# Sheet3.net
KiCad netlist of a schematic drawn in Altium Designer
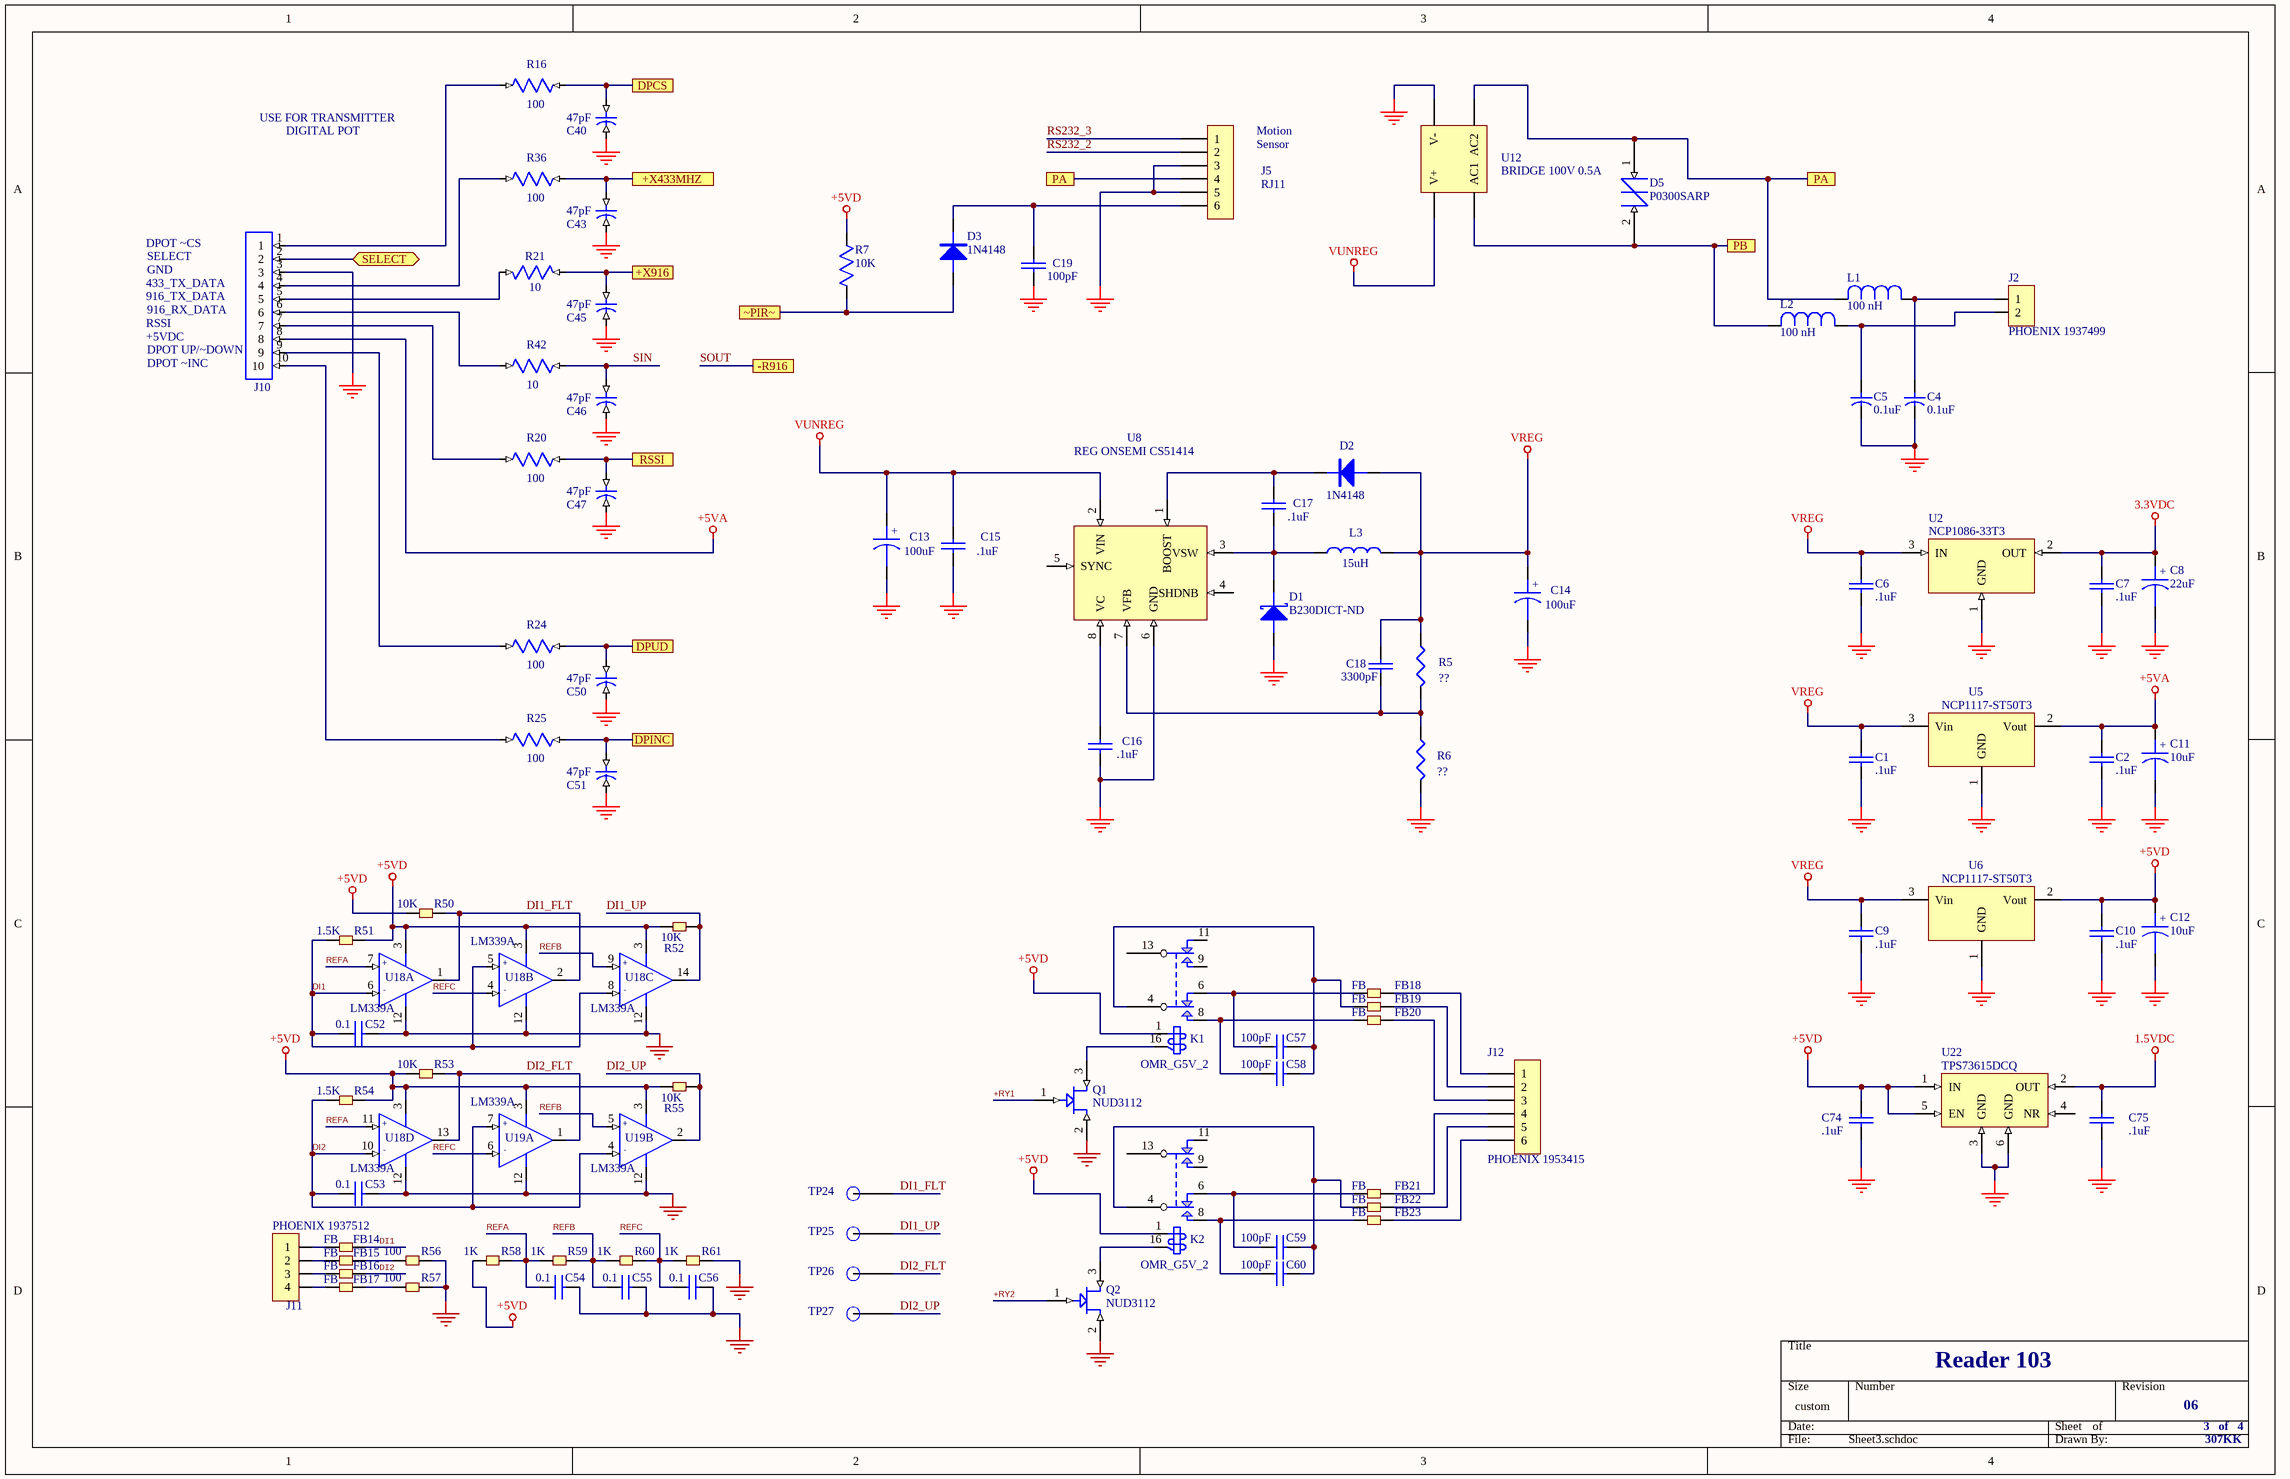
[diagram p0: Sheet3.schdoc]

(export (version "E")
  (design (tool "Eeschema 10.0.6"))
  (components
    (comp (ref "C1")
      (value ".1uF")
      (footprint "0603")
      (description "Capacitor")
      (libsource (lib "*") (part "CAP"))
    )
    (comp (ref "C2")
      (value ".1uF")
      (footprint "0603")
      (description "Capacitor")
      (libsource (lib "*") (part "CAP"))
    )
    (comp (ref "C4") (value "0.1uF") (footprint "0603") (libsource (lib "*") (part "C_0603")))
    (comp (ref "C5") (value "0.1uF") (footprint "0603") (libsource (lib "*") (part "C_0603")))
    (comp (ref "C6")
      (value ".1uF")
      (footprint "0603")
      (description "Capacitor")
      (libsource (lib "*") (part "CAP"))
    )
    (comp (ref "C7")
      (value ".1uF")
      (footprint "0603")
      (description "Capacitor")
      (libsource (lib "*") (part "CAP"))
    )
    (comp (ref "C8")
      (value "22uF")
      (footprint "CAP A CASE")
      (description "Capacitor")
      (libsource (lib "*") (part "CAPACITOR POL"))
    )
    (comp (ref "C9")
      (value ".1uF")
      (footprint "0603")
      (description "Capacitor")
      (libsource (lib "*") (part "CAP"))
    )
    (comp (ref "C10")
      (value ".1uF")
      (footprint "0603")
      (description "Capacitor")
      (libsource (lib "*") (part "CAP"))
    )
    (comp (ref "C11")
      (value "10uF")
      (footprint "CAP A CASE")
      (description "Capacitor")
      (libsource (lib "*") (part "CAPACITOR POL"))
    )
    (comp (ref "C12")
      (value "10uF")
      (footprint "CAP A CASE")
      (description "Capacitor")
      (libsource (lib "*") (part "CAPACITOR POL"))
    )
    (comp (ref "C13")
      (value "100uF")
      (footprint "CAP D CASE")
      (description "Capacitor")
      (libsource (lib "*") (part "CAPACITOR POL"))
    )
    (comp (ref "C14")
      (value "100uF")
      (footprint "CAP D CASE")
      (description "Capacitor")
      (libsource (lib "*") (part "CAPACITOR POL"))
    )
    (comp (ref "C15")
      (value ".1uF")
      (footprint "0603")
      (description "Capacitor")
      (libsource (lib "*") (part "CAP"))
    )
    (comp (ref "C16")
      (value ".1uF")
      (footprint "0603")
      (description "Capacitor")
      (libsource (lib "*") (part "CAP"))
    )
    (comp (ref "C17")
      (value ".1uF")
      (footprint "0603")
      (description "Capacitor")
      (libsource (lib "*") (part "CAP"))
    )
    (comp (ref "C18")
      (value "3300pF")
      (footprint "0603")
      (description "Capacitor")
      (libsource (lib "*") (part "CAP"))
    )
    (comp (ref "C19")
      (value "100pF")
      (footprint "0603")
      (description "Capacitor")
      (libsource (lib "*") (part "CAP"))
    )
    (comp (ref "C40") (value "47pF") (footprint "C0603") (libsource (lib "*") (part "C0603")))
    (comp (ref "C43") (value "47pF") (footprint "C0603") (libsource (lib "*") (part "C0603")))
    (comp (ref "C45") (value "47pF") (footprint "C0603") (libsource (lib "*") (part "C0603")))
    (comp (ref "C46") (value "47pF") (footprint "C0603") (libsource (lib "*") (part "C0603")))
    (comp (ref "C47") (value "47pF") (footprint "C0603") (libsource (lib "*") (part "C0603")))
    (comp (ref "C50") (value "47pF") (footprint "C0603") (libsource (lib "*") (part "C0603")))
    (comp (ref "C51") (value "47pF") (footprint "C0603") (libsource (lib "*") (part "C0603")))
    (comp (ref "C52") (value "0.1") (footprint "0805") (libsource (lib "*") (part "CAP NP_1")))
    (comp (ref "C53") (value "0.1") (footprint "0805") (libsource (lib "*") (part "CAP NP_1")))
    (comp (ref "C54") (value "0.1") (footprint "0805") (libsource (lib "*") (part "CAP NP_1")))
    (comp (ref "C55") (value "0.1") (footprint "0805") (libsource (lib "*") (part "CAP NP_1")))
    (comp (ref "C56") (value "0.1") (footprint "0805") (libsource (lib "*") (part "CAP NP_1")))
    (comp (ref "C57") (value "100pF") (footprint "SM/C_0805") (libsource (lib "*") (part "CAP NP_1")))
    (comp (ref "C58") (value "100pF") (footprint "SM/C_0805") (libsource (lib "*") (part "CAP NP_1")))
    (comp (ref "C59") (value "100pF") (footprint "SM/C_0805") (libsource (lib "*") (part "CAP NP_1")))
    (comp (ref "C60") (value "100pF") (footprint "SM/C_0805") (libsource (lib "*") (part "CAP NP_1")))
    (comp (ref "C74")
      (value ".1uF")
      (footprint "0603")
      (description "Capacitor")
      (libsource (lib "*") (part "CAP"))
    )
    (comp (ref "C75")
      (value ".1uF")
      (footprint "0603")
      (description "Capacitor")
      (libsource (lib "*") (part "CAP"))
    )
    (comp (ref "D1")
      (value "B230DICT-ND")
      (footprint "DIODE SMB")
      (description "Schottky Diode")
      (libsource (lib "*") (part "DIODE SCHOTTKY"))
    )
    (comp (ref "D2")
      (value "1N4148")
      (footprint "SOD123")
      (description "Diode")
      (libsource (lib "*") (part "DIODE"))
    )
    (comp (ref "D3")
      (value "1N4148")
      (footprint "SOD123")
      (description "Diode")
      (libsource (lib "*") (part "DIODE"))
    )
    (comp (ref "D5") (value "P0300SARP") (footprint "TRANSORB_1") (libsource (lib "*") (part "TRANSORB")))
    (comp (ref "FB14") (value "FB") (footprint "0603") (libsource (lib "*") (part "FB")))
    (comp (ref "FB15") (value "FB") (footprint "0603") (libsource (lib "*") (part "FB")))
    (comp (ref "FB16") (value "FB") (footprint "0603") (libsource (lib "*") (part "FB")))
    (comp (ref "FB17") (value "FB") (footprint "0603") (libsource (lib "*") (part "FB")))
    (comp (ref "FB18") (value "FB") (footprint "SM/R_1206") (libsource (lib "*") (part "FB")))
    (comp (ref "FB19") (value "FB") (footprint "SM/R_1206") (libsource (lib "*") (part "FB")))
    (comp (ref "FB20") (value "FB") (footprint "SM/R_1206") (libsource (lib "*") (part "FB")))
    (comp (ref "FB21") (value "FB") (footprint "SM/R_1206") (libsource (lib "*") (part "FB")))
    (comp (ref "FB22") (value "FB") (footprint "SM/R_1206") (libsource (lib "*") (part "FB")))
    (comp (ref "FB23") (value "FB") (footprint "SM/R_1206") (libsource (lib "*") (part "FB")))
    (comp (ref "J2")
      (value "PHOENIX 1937499")
      (footprint "CONN PHOENIX 1803227-2")
      (description "Connector")
      (libsource (lib "*") (part "CON2"))
    )
    (comp (ref "J5")
      (value "RJ11")
      (footprint "RJ11")
      (description "Connector")
      (libsource (lib "*") (part "CON6"))
    )
    (comp (ref "J10") (value "1X10 HEADER") (footprint "1X10 HEADER") (libsource (lib "*") (part "HDR10")))
    (comp (ref "J11")
      (value "PHOENIX 1937512")
      (footprint "CONN PHOENIX 1803293-4")
      (libsource (lib "*") (part "CON4"))
    )
    (comp (ref "J12")
      (value "PHOENIX 1953415")
      (footprint "CONN PHOENIX 1953211-6")
      (description "Connector")
      (libsource (lib "*") (part "CON6"))
    )
    (comp (ref "K1") (value "OMR_G5V_2") (footprint "RELAY44") (libsource (lib "*") (part "OMRON_G5V_3")))
    (comp (ref "K2") (value "OMR_G5V_2") (footprint "RELAY44") (libsource (lib "*") (part "OMRON_G5V_3")))
    (comp (ref "L1") (value "100 nH") (footprint "0603") (libsource (lib "*") (part "INDUCTOR_1")))
    (comp (ref "L2") (value "100 nH") (footprint "0603") (libsource (lib "*") (part "INDUCTOR_1")))
    (comp (ref "L3")
      (value "15uH")
      (footprint "COIL COILTRONICS UP2B-150")
      (libsource (lib "*") (part "INDUCTOR1"))
    )
    (comp (ref "Q1")
      (value "NUD3112")
      (footprint "SOT23")
      (libsource (lib "*") (part "INDUCTIVE LOAD DRIVER"))
    )
    (comp (ref "Q2")
      (value "NUD3112")
      (footprint "SOT23")
      (libsource (lib "*") (part "INDUCTIVE LOAD DRIVER"))
    )
    (comp (ref "R5") (value "??") (footprint "0603") (libsource (lib "*") (part "RES1")))
    (comp (ref "R6") (value "??") (footprint "0603") (libsource (lib "*") (part "RES1")))
    (comp (ref "R7") (value "10K") (footprint "0603") (libsource (lib "*") (part "R_0603")))
    (comp (ref "R16") (value "100") (footprint "R0603") (libsource (lib "*") (part "R0603")))
    (comp (ref "R20") (value "100") (footprint "R0603") (libsource (lib "*") (part "R0603")))
    (comp (ref "R21") (value "10") (footprint "R-603") (libsource (lib "*") (part "R_603")))
    (comp (ref "R24") (value "100") (footprint "R0603") (libsource (lib "*") (part "R0603")))
    (comp (ref "R25") (value "100") (footprint "R0603") (libsource (lib "*") (part "R0603")))
    (comp (ref "R36") (value "100") (footprint "R0603") (libsource (lib "*") (part "R0603")))
    (comp (ref "R42") (value "10") (footprint "R0603") (libsource (lib "*") (part "R0603")))
    (comp (ref "R50") (value "10K") (footprint "0805") (libsource (lib "*") (part "RS")))
    (comp (ref "R51") (value "1.5K") (footprint "0805") (libsource (lib "*") (part "RS")))
    (comp (ref "R52") (value "10K") (footprint "0805") (libsource (lib "*") (part "RS")))
    (comp (ref "R53") (value "10K") (footprint "0805") (libsource (lib "*") (part "RS")))
    (comp (ref "R54") (value "1.5K") (footprint "0805") (libsource (lib "*") (part "RS")))
    (comp (ref "R55") (value "10K") (footprint "0805") (libsource (lib "*") (part "RS")))
    (comp (ref "R56") (value "100") (footprint "0805") (libsource (lib "*") (part "RS")))
    (comp (ref "R57") (value "100") (footprint "0805") (libsource (lib "*") (part "RS")))
    (comp (ref "R58") (value "1K") (footprint "0805") (libsource (lib "*") (part "RS")))
    (comp (ref "R59") (value "1K") (footprint "0805") (libsource (lib "*") (part "RS")))
    (comp (ref "R60") (value "1K") (footprint "0805") (libsource (lib "*") (part "RS")))
    (comp (ref "R61") (value "1K") (footprint "0805") (libsource (lib "*") (part "RS")))
    (comp (ref "TP24") (value "TP") (footprint "TESTPOINT-1") (libsource (lib "*") (part "TESTPOINT_1")))
    (comp (ref "TP25") (value "TP") (footprint "TESTPOINT-1") (libsource (lib "*") (part "TESTPOINT_1")))
    (comp (ref "TP26") (value "TP") (footprint "TESTPOINT-1") (libsource (lib "*") (part "TESTPOINT_1")))
    (comp (ref "TP27") (value "TP") (footprint "TESTPOINT-1") (libsource (lib "*") (part "TESTPOINT_1")))
    (comp (ref "U2")
      (value "NCP1086-33T3")
      (footprint "SOT223 REG GOI")
      (libsource (lib "*") (part "REG GOI"))
    )
    (comp (ref "U5")
      (value "NCP1117-ST50T3")
      (footprint "SOT223 REG")
      (libsource (lib "*") (part "REG REVERSED"))
    )
    (comp (ref "U6")
      (value "NCP1117-ST50T3")
      (footprint "SOT223 REG")
      (libsource (lib "*") (part "REG REVERSED"))
    )
    (comp (ref "U8")
      (value "REG ONSEMI CS51414")
      (footprint "SO8")
      (libsource (lib "*") (part "REG ONSEMI CS51414"))
    )
    (comp (ref "U12")
      (value "BRIDGE 100V 0.5A")
      (footprint "BRIDGE")
      (description "Diode Bridge")
      (libsource (lib "*") (part "BRIDGE2"))
    )
    (comp (ref "U18") (value "LM339A") (footprint "SO14") (libsource (lib "*") (part "LM339")))
    (comp (ref "U19") (value "LM339A") (footprint "SO14") (libsource (lib "*") (part "LM339")))
    (comp (ref "U22")
      (value "TPS73615DCQ")
      (footprint "SOT223-5")
      (libsource (lib "*") (part "REG SOT223-5"))
    )
  )
  (nets
    (net (code "1") (name "+5VA") (class "Default")
      (node (ref "C11") (pin "1") (pinfunction "1_1") (pintype "passive"))
      (node (ref "C2") (pin "1") (pinfunction "1_1") (pintype "passive"))
      (node (ref "J10") (pin "8") (pinfunction "8_8") (pintype "input"))
      (node (ref "U5") (pin "2") (pinfunction "Vout_2") (pintype "passive"))
    )
    (net (code "2") (name "+5VD") (class "Default")
      (node (ref "C10") (pin "1") (pinfunction "1_1") (pintype "passive"))
      (node (ref "C12") (pin "1") (pinfunction "1_1") (pintype "passive"))
      (node (ref "C74") (pin "1") (pinfunction "1_1") (pintype "passive"))
      (node (ref "K1") (pin "1") (pinfunction "COIL1_1") (pintype "passive"))
      (node (ref "K2") (pin "1") (pinfunction "COIL1_1") (pintype "passive"))
      (node (ref "R50") (pin "2") (pinfunction "2_2") (pintype "passive"))
      (node (ref "R51") (pin "1") (pinfunction "1_1") (pintype "passive"))
      (node (ref "R52") (pin "2") (pinfunction "2_2") (pintype "passive"))
      (node (ref "R53") (pin "2") (pinfunction "2_2") (pintype "passive"))
      (node (ref "R54") (pin "1") (pinfunction "1_1") (pintype "passive"))
      (node (ref "R55") (pin "2") (pinfunction "2_2") (pintype "passive"))
      (node (ref "R58") (pin "2") (pinfunction "2_2") (pintype "passive"))
      (node (ref "R7") (pin "1") (pinfunction "A_1") (pintype "passive"))
      (node (ref "U18") (pin "3") (pinfunction "V+_3") (pintype "power_in"))
      (node (ref "U19") (pin "3") (pinfunction "V+_3") (pintype "power_in"))
      (node (ref "U22") (pin "1") (pinfunction "IN_1") (pintype "input"))
      (node (ref "U22") (pin "5") (pinfunction "EN_5") (pintype "input"))
      (node (ref "U6") (pin "2") (pinfunction "Vout_2") (pintype "passive"))
    )
    (net (code "3") (name "/+RY1") (class "Default")
      (node (ref "Q1") (pin "1") (pinfunction "G_1") (pintype "input"))
    )
    (net (code "4") (name "/+RY2") (class "Default")
      (node (ref "Q2") (pin "1") (pinfunction "G_1") (pintype "input"))
    )
    (net (code "5") (name "/+X433MHZ") (class "Default")
      (node (ref "C43") (pin "1") (pinfunction "A_1") (pintype "input"))
      (node (ref "R36") (pin "2") (pinfunction "B_2") (pintype "input"))
    )
    (net (code "6") (name "/+X916") (class "Default")
      (node (ref "C45") (pin "1") (pinfunction "A_1") (pintype "input"))
      (node (ref "R21") (pin "1") (pinfunction "A_1") (pintype "input"))
    )
    (net (code "7") (name "/DI1") (class "Default")
      (node (ref "C52") (pin "1") (pinfunction "1_1") (pintype "passive"))
      (node (ref "FB14") (pin "1") (pinfunction "1_1") (pintype "passive"))
      (node (ref "R51") (pin "2") (pinfunction "2_2") (pintype "passive"))
      (node (ref "U18") (pin "5") (pinfunction "+_5") (pintype "input"))
      (node (ref "U18") (pin "6") (pinfunction "-_6") (pintype "input"))
      (node (ref "U18") (pin "8") (pinfunction "-_8") (pintype "input"))
    )
    (net (code "8") (name "/DI1_FLT") (class "Default")
      (node (ref "R50") (pin "1") (pinfunction "1_1") (pintype "passive"))
      (node (ref "TP24") (pin "1") (pinfunction "TP_1") (pintype "passive"))
      (node (ref "U18") (pin "1") (pinfunction "OUT_1") (pintype "open_collector"))
      (node (ref "U18") (pin "2") (pinfunction "OUT_2") (pintype "open_collector"))
    )
    (net (code "9") (name "/DI1_UP") (class "Default")
      (node (ref "R52") (pin "1") (pinfunction "1_1") (pintype "passive"))
      (node (ref "TP25") (pin "1") (pinfunction "TP_1") (pintype "passive"))
      (node (ref "U18") (pin "14") (pinfunction "OUT_14") (pintype "open_collector"))
    )
    (net (code "10") (name "/DI2") (class "Default")
      (node (ref "C53") (pin "1") (pinfunction "1_1") (pintype "passive"))
      (node (ref "FB16") (pin "1") (pinfunction "1_1") (pintype "passive"))
      (node (ref "R54") (pin "2") (pinfunction "2_2") (pintype "passive"))
      (node (ref "U18") (pin "10") (pinfunction "-_10") (pintype "input"))
      (node (ref "U19") (pin "4") (pinfunction "-_4") (pintype "input"))
      (node (ref "U19") (pin "7") (pinfunction "+_7") (pintype "input"))
    )
    (net (code "11") (name "/DI2_FLT") (class "Default")
      (node (ref "R53") (pin "1") (pinfunction "1_1") (pintype "passive"))
      (node (ref "TP26") (pin "1") (pinfunction "TP_1") (pintype "passive"))
      (node (ref "U18") (pin "13") (pinfunction "OUT_13") (pintype "open_collector"))
      (node (ref "U19") (pin "1") (pinfunction "OUT_1") (pintype "open_collector"))
    )
    (net (code "12") (name "/DI2_UP") (class "Default")
      (node (ref "R55") (pin "1") (pinfunction "1_1") (pintype "passive"))
      (node (ref "TP27") (pin "1") (pinfunction "TP_1") (pintype "passive"))
      (node (ref "U19") (pin "2") (pinfunction "OUT_2") (pintype "open_collector"))
    )
    (net (code "13") (name "/DPCS") (class "Default")
      (node (ref "C40") (pin "1") (pinfunction "A_1") (pintype "input"))
      (node (ref "R16") (pin "2") (pinfunction "B_2") (pintype "input"))
    )
    (net (code "14") (name "/DPINC") (class "Default")
      (node (ref "C51") (pin "1") (pinfunction "A_1") (pintype "input"))
      (node (ref "R25") (pin "2") (pinfunction "B_2") (pintype "input"))
    )
    (net (code "15") (name "/DPUD") (class "Default")
      (node (ref "C50") (pin "1") (pinfunction "A_1") (pintype "input"))
      (node (ref "R24") (pin "2") (pinfunction "B_2") (pintype "input"))
    )
    (net (code "16") (name "/PA") (class "Default")
      (node (ref "D5") (pin "1") (pinfunction "1_1") (pintype "input"))
      (node (ref "J5") (pin "4") (pinfunction "4_4") (pintype "passive"))
      (node (ref "L1") (pin "1") (pinfunction "B_1") (pintype "passive"))
      (node (ref "U12") (pin "AC2") (pinfunction "AC2_AC2") (pintype "passive"))
    )
    (net (code "17") (name "/PB") (class "Default")
      (node (ref "D5") (pin "2") (pinfunction "2_2") (pintype "input"))
      (node (ref "L2") (pin "1") (pinfunction "B_1") (pintype "passive"))
      (node (ref "U12") (pin "AC1") (pinfunction "AC1_AC1") (pintype "passive"))
    )
    (net (code "18") (name "/REFA") (class "Default")
      (node (ref "C54") (pin "1") (pinfunction "1_1") (pintype "passive"))
      (node (ref "R58") (pin "1") (pinfunction "1_1") (pintype "passive"))
      (node (ref "R59") (pin "2") (pinfunction "2_2") (pintype "passive"))
      (node (ref "U18") (pin "11") (pinfunction "+_11") (pintype "input"))
      (node (ref "U18") (pin "7") (pinfunction "+_7") (pintype "input"))
    )
    (net (code "19") (name "/REFB") (class "Default")
      (node (ref "C55") (pin "1") (pinfunction "1_1") (pintype "passive"))
      (node (ref "R59") (pin "1") (pinfunction "1_1") (pintype "passive"))
      (node (ref "R60") (pin "2") (pinfunction "2_2") (pintype "passive"))
      (node (ref "U18") (pin "9") (pinfunction "+_9") (pintype "input"))
      (node (ref "U19") (pin "5") (pinfunction "+_5") (pintype "input"))
    )
    (net (code "20") (name "/REFC") (class "Default")
      (node (ref "C56") (pin "1") (pinfunction "1_1") (pintype "passive"))
      (node (ref "R60") (pin "1") (pinfunction "1_1") (pintype "passive"))
      (node (ref "R61") (pin "2") (pinfunction "2_2") (pintype "passive"))
      (node (ref "U18") (pin "4") (pinfunction "-_4") (pintype "input"))
      (node (ref "U19") (pin "6") (pinfunction "-_6") (pintype "input"))
    )
    (net (code "21") (name "/RS232_2") (class "Default")
      (node (ref "J5") (pin "2") (pinfunction "2_2") (pintype "passive"))
    )
    (net (code "22") (name "/RS232_3") (class "Default")
      (node (ref "J5") (pin "1") (pinfunction "1_1") (pintype "passive"))
    )
    (net (code "23") (name "/RSSI") (class "Default")
      (node (ref "C47") (pin "1") (pinfunction "A_1") (pintype "input"))
      (node (ref "R20") (pin "2") (pinfunction "B_2") (pintype "input"))
    )
    (net (code "24") (name "/SELECT") (class "Default")
      (node (ref "J10") (pin "2") (pinfunction "2_2") (pintype "input"))
    )
    (net (code "25") (name "/SIN") (class "Default")
      (node (ref "C46") (pin "1") (pinfunction "A_1") (pintype "input"))
      (node (ref "R42") (pin "2") (pinfunction "B_2") (pintype "input"))
    )
    (net (code "27") (name "/~PIR~") (class "Default")
      (node (ref "D3") (pin "A") (pinfunction "A_A") (pintype "passive"))
      (node (ref "R7") (pin "2") (pinfunction "B_2") (pintype "passive"))
    )
    (net (code "28") (name "1.5VDC") (class "Default")
      (node (ref "C75") (pin "1") (pinfunction "1_1") (pintype "passive"))
      (node (ref "U22") (pin "2") (pinfunction "OUT_2") (pintype "input"))
    )
    (net (code "29") (name "3.3VDC") (class "Default")
      (node (ref "C7") (pin "1") (pinfunction "1_1") (pintype "passive"))
      (node (ref "C8") (pin "1") (pinfunction "1_1") (pintype "passive"))
      (node (ref "U2") (pin "2") (pinfunction "OUT_2") (pintype "input"))
    )
    (net (code "30") (name "GND_COM") (class "Default")
      (node (ref "C1") (pin "2") (pinfunction "2_2") (pintype "passive"))
      (node (ref "C10") (pin "2") (pinfunction "2_2") (pintype "passive"))
      (node (ref "C11") (pin "2") (pinfunction "2_2") (pintype "passive"))
      (node (ref "C12") (pin "2") (pinfunction "2_2") (pintype "passive"))
      (node (ref "C13") (pin "2") (pinfunction "2_2") (pintype "passive"))
      (node (ref "C14") (pin "2") (pinfunction "2_2") (pintype "passive"))
      (node (ref "C15") (pin "2") (pinfunction "2_2") (pintype "passive"))
      (node (ref "C16") (pin "2") (pinfunction "2_2") (pintype "passive"))
      (node (ref "C19") (pin "2") (pinfunction "2_2") (pintype "passive"))
      (node (ref "C2") (pin "2") (pinfunction "2_2") (pintype "passive"))
      (node (ref "C4") (pin "2") (pinfunction "B_2") (pintype "passive"))
      (node (ref "C40") (pin "2") (pinfunction "B_2") (pintype "input"))
      (node (ref "C43") (pin "2") (pinfunction "B_2") (pintype "input"))
      (node (ref "C45") (pin "2") (pinfunction "B_2") (pintype "input"))
      (node (ref "C46") (pin "2") (pinfunction "B_2") (pintype "input"))
      (node (ref "C47") (pin "2") (pinfunction "B_2") (pintype "input"))
      (node (ref "C5") (pin "2") (pinfunction "B_2") (pintype "passive"))
      (node (ref "C50") (pin "2") (pinfunction "B_2") (pintype "input"))
      (node (ref "C51") (pin "2") (pinfunction "B_2") (pintype "input"))
      (node (ref "C52") (pin "2") (pinfunction "2_2") (pintype "passive"))
      (node (ref "C53") (pin "2") (pinfunction "2_2") (pintype "passive"))
      (node (ref "C54") (pin "2") (pinfunction "2_2") (pintype "passive"))
      (node (ref "C55") (pin "2") (pinfunction "2_2") (pintype "passive"))
      (node (ref "C56") (pin "2") (pinfunction "2_2") (pintype "passive"))
      (node (ref "C6") (pin "2") (pinfunction "2_2") (pintype "passive"))
      (node (ref "C7") (pin "2") (pinfunction "2_2") (pintype "passive"))
      (node (ref "C74") (pin "2") (pinfunction "2_2") (pintype "passive"))
      (node (ref "C75") (pin "2") (pinfunction "2_2") (pintype "passive"))
      (node (ref "C8") (pin "2") (pinfunction "2_2") (pintype "passive"))
      (node (ref "C9") (pin "2") (pinfunction "2_2") (pintype "passive"))
      (node (ref "D1") (pin "A") (pinfunction "A_A") (pintype "passive"))
      (node (ref "J10") (pin "3") (pinfunction "3_3") (pintype "input"))
      (node (ref "J5") (pin "3") (pinfunction "3_3") (pintype "passive"))
      (node (ref "J5") (pin "5") (pinfunction "5_5") (pintype "passive"))
      (node (ref "Q1") (pin "2") (pinfunction "S_2") (pintype "input"))
      (node (ref "Q2") (pin "2") (pinfunction "S_2") (pintype "input"))
      (node (ref "R56") (pin "1") (pinfunction "1_1") (pintype "passive"))
      (node (ref "R57") (pin "1") (pinfunction "1_1") (pintype "passive"))
      (node (ref "R6") (pin "2") (pinfunction "2_2") (pintype "passive"))
      (node (ref "R61") (pin "1") (pinfunction "1_1") (pintype "passive"))
      (node (ref "U12") (pin "V-") (pinfunction "V-_V-") (pintype "passive"))
      (node (ref "U18") (pin "12") (pinfunction "V-_12") (pintype "power_in"))
      (node (ref "U19") (pin "12") (pinfunction "V-_12") (pintype "power_in"))
      (node (ref "U2") (pin "1") (pinfunction "GND_1") (pintype "input"))
      (node (ref "U22") (pin "3") (pinfunction "GND_3") (pintype "input"))
      (node (ref "U22") (pin "6") (pinfunction "GND_6") (pintype "input"))
      (node (ref "U5") (pin "1") (pinfunction "GND_1") (pintype "passive"))
      (node (ref "U6") (pin "1") (pinfunction "GND_1") (pintype "passive"))
      (node (ref "U8") (pin "6") (pinfunction "GND_6") (pintype "input"))
    )
    (net (code "31") (name "Net-(C4-A)") (class "Default")
      (node (ref "C4") (pin "1") (pinfunction "A_1") (pintype "passive"))
      (node (ref "J2") (pin "1") (pinfunction "1_1") (pintype "passive"))
      (node (ref "L1") (pin "2") (pinfunction "A_2") (pintype "passive"))
    )
    (net (code "32") (name "Net-(C5-A)") (class "Default")
      (node (ref "C5") (pin "1") (pinfunction "A_1") (pintype "passive"))
      (node (ref "J2") (pin "2") (pinfunction "2_2") (pintype "passive"))
      (node (ref "L2") (pin "2") (pinfunction "A_2") (pintype "passive"))
    )
    (net (code "33") (name "Net-(C19-Pad1)") (class "Default")
      (node (ref "C19") (pin "1") (pinfunction "1_1") (pintype "passive"))
      (node (ref "D3") (pin "K") (pinfunction "K_K") (pintype "passive"))
      (node (ref "J5") (pin "6") (pinfunction "6_6") (pintype "passive"))
    )
    (net (code "34") (name "Net-(FB14-Pad2)") (class "Default")
      (node (ref "FB14") (pin "2") (pinfunction "2_2") (pintype "passive"))
      (node (ref "J11") (pin "1") (pinfunction "1_1") (pintype "passive"))
    )
    (net (code "35") (name "Net-(FB15-Pad1)") (class "Default")
      (node (ref "FB15") (pin "1") (pinfunction "1_1") (pintype "passive"))
      (node (ref "R56") (pin "2") (pinfunction "2_2") (pintype "passive"))
    )
    (net (code "36") (name "Net-(FB15-Pad2)") (class "Default")
      (node (ref "FB15") (pin "2") (pinfunction "2_2") (pintype "passive"))
      (node (ref "J11") (pin "2") (pinfunction "2_2") (pintype "passive"))
    )
    (net (code "37") (name "Net-(FB16-Pad2)") (class "Default")
      (node (ref "FB16") (pin "2") (pinfunction "2_2") (pintype "passive"))
      (node (ref "J11") (pin "3") (pinfunction "3_3") (pintype "passive"))
    )
    (net (code "38") (name "Net-(FB17-Pad1)") (class "Default")
      (node (ref "FB17") (pin "1") (pinfunction "1_1") (pintype "passive"))
      (node (ref "R57") (pin "2") (pinfunction "2_2") (pintype "passive"))
    )
    (net (code "39") (name "Net-(FB17-Pad2)") (class "Default")
      (node (ref "FB17") (pin "2") (pinfunction "2_2") (pintype "passive"))
      (node (ref "J11") (pin "4") (pinfunction "4_4") (pintype "passive"))
    )
    (net (code "40") (name "Net-(FB18-Pad1)") (class "Default")
      (node (ref "FB18") (pin "1") (pinfunction "1_1") (pintype "passive"))
      (node (ref "J12") (pin "1") (pinfunction "1_1") (pintype "passive"))
    )
    (net (code "41") (name "Net-(FB19-Pad1)") (class "Default")
      (node (ref "FB19") (pin "1") (pinfunction "1_1") (pintype "passive"))
      (node (ref "J12") (pin "2") (pinfunction "2_2") (pintype "passive"))
    )
    (net (code "42") (name "Net-(FB20-Pad1)") (class "Default")
      (node (ref "FB20") (pin "1") (pinfunction "1_1") (pintype "passive"))
      (node (ref "J12") (pin "3") (pinfunction "3_3") (pintype "passive"))
    )
    (net (code "43") (name "Net-(FB21-Pad1)") (class "Default")
      (node (ref "FB21") (pin "1") (pinfunction "1_1") (pintype "passive"))
      (node (ref "J12") (pin "4") (pinfunction "4_4") (pintype "passive"))
    )
    (net (code "44") (name "Net-(FB22-Pad1)") (class "Default")
      (node (ref "FB22") (pin "1") (pinfunction "1_1") (pintype "passive"))
      (node (ref "J12") (pin "5") (pinfunction "5_5") (pintype "passive"))
    )
    (net (code "45") (name "Net-(FB23-Pad1)") (class "Default")
      (node (ref "FB23") (pin "1") (pinfunction "1_1") (pintype "passive"))
      (node (ref "J12") (pin "6") (pinfunction "6_6") (pintype "passive"))
    )
    (net (code "46") (name "Net-(K1-COIL2)") (class "Default")
      (node (ref "K1") (pin "16") (pinfunction "COIL2_16") (pintype "passive"))
      (node (ref "Q1") (pin "3") (pinfunction "D_3") (pintype "input"))
    )
    (net (code "47") (name "Net-(K1-COMMON2)") (class "Default")
      (node (ref "C57") (pin "2") (pinfunction "2_2") (pintype "passive"))
      (node (ref "C58") (pin "2") (pinfunction "2_2") (pintype "passive"))
      (node (ref "FB19") (pin "2") (pinfunction "2_2") (pintype "passive"))
      (node (ref "K1") (pin "4") (pinfunction "COMMON2_4") (pintype "passive"))
    )
    (net (code "48") (name "Net-(K1-NC2)") (class "Default")
      (node (ref "C57") (pin "1") (pinfunction "1_1") (pintype "passive"))
      (node (ref "FB18") (pin "2") (pinfunction "2_2") (pintype "passive"))
      (node (ref "K1") (pin "6") (pinfunction "NC2_6") (pintype "passive"))
    )
    (net (code "49") (name "Net-(K1-NO2)") (class "Default")
      (node (ref "C58") (pin "1") (pinfunction "1_1") (pintype "passive"))
      (node (ref "FB20") (pin "2") (pinfunction "2_2") (pintype "passive"))
      (node (ref "K1") (pin "8") (pinfunction "NO2_8") (pintype "passive"))
    )
    (net (code "50") (name "Net-(K2-COIL2)") (class "Default")
      (node (ref "K2") (pin "16") (pinfunction "COIL2_16") (pintype "passive"))
      (node (ref "Q2") (pin "3") (pinfunction "D_3") (pintype "input"))
    )
    (net (code "51") (name "Net-(K2-COMMON2)") (class "Default")
      (node (ref "C59") (pin "2") (pinfunction "2_2") (pintype "passive"))
      (node (ref "C60") (pin "2") (pinfunction "2_2") (pintype "passive"))
      (node (ref "FB22") (pin "2") (pinfunction "2_2") (pintype "passive"))
      (node (ref "K2") (pin "4") (pinfunction "COMMON2_4") (pintype "passive"))
    )
    (net (code "52") (name "Net-(K2-NC2)") (class "Default")
      (node (ref "C59") (pin "1") (pinfunction "1_1") (pintype "passive"))
      (node (ref "FB21") (pin "2") (pinfunction "2_2") (pintype "passive"))
      (node (ref "K2") (pin "6") (pinfunction "NC2_6") (pintype "passive"))
    )
    (net (code "53") (name "Net-(K2-NO2)") (class "Default")
      (node (ref "C60") (pin "1") (pinfunction "1_1") (pintype "passive"))
      (node (ref "FB23") (pin "2") (pinfunction "2_2") (pintype "passive"))
      (node (ref "K2") (pin "8") (pinfunction "NO2_8") (pintype "passive"))
    )
    (net (code "54") (name "Net-(R16-A)") (class "Default")
      (node (ref "J10") (pin "1") (pinfunction "1_1") (pintype "input"))
      (node (ref "R16") (pin "1") (pinfunction "A_1") (pintype "input"))
    )
    (net (code "55") (name "Net-(R20-A)") (class "Default")
      (node (ref "J10") (pin "7") (pinfunction "7_7") (pintype "input"))
      (node (ref "R20") (pin "1") (pinfunction "A_1") (pintype "input"))
    )
    (net (code "56") (name "Net-(R21-B)") (class "Default")
      (node (ref "J10") (pin "5") (pinfunction "5_5") (pintype "input"))
      (node (ref "R21") (pin "2") (pinfunction "B_2") (pintype "input"))
    )
    (net (code "57") (name "Net-(R24-A)") (class "Default")
      (node (ref "J10") (pin "9") (pinfunction "9_9") (pintype "input"))
      (node (ref "R24") (pin "1") (pinfunction "A_1") (pintype "input"))
    )
    (net (code "58") (name "Net-(R25-A)") (class "Default")
      (node (ref "J10") (pin "10") (pinfunction "10_10") (pintype "input"))
      (node (ref "R25") (pin "1") (pinfunction "A_1") (pintype "input"))
    )
    (net (code "59") (name "Net-(R36-A)") (class "Default")
      (node (ref "J10") (pin "4") (pinfunction "4_4") (pintype "input"))
      (node (ref "R36") (pin "1") (pinfunction "A_1") (pintype "input"))
    )
    (net (code "60") (name "Net-(R42-A)") (class "Default")
      (node (ref "J10") (pin "6") (pinfunction "6_6") (pintype "input"))
      (node (ref "R42") (pin "1") (pinfunction "A_1") (pintype "input"))
    )
    (net (code "61") (name "Net-(U8-BOOST)") (class "Default")
      (node (ref "C17") (pin "1") (pinfunction "1_1") (pintype "passive"))
      (node (ref "D2") (pin "K") (pinfunction "K_K") (pintype "passive"))
      (node (ref "U8") (pin "1") (pinfunction "BOOST_1") (pintype "input"))
    )
    (net (code "62") (name "Net-(U8-VC)") (class "Default")
      (node (ref "C16") (pin "1") (pinfunction "1_1") (pintype "passive"))
      (node (ref "U8") (pin "8") (pinfunction "VC_8") (pintype "input"))
    )
    (net (code "63") (name "Net-(U8-VFB)") (class "Default")
      (node (ref "C18") (pin "2") (pinfunction "2_2") (pintype "passive"))
      (node (ref "R5") (pin "2") (pinfunction "2_2") (pintype "passive"))
      (node (ref "R6") (pin "1") (pinfunction "1_1") (pintype "passive"))
      (node (ref "U8") (pin "7") (pinfunction "VFB_7") (pintype "input"))
    )
    (net (code "64") (name "Net-(U8-VSW)") (class "Default")
      (node (ref "C17") (pin "2") (pinfunction "2_2") (pintype "passive"))
      (node (ref "D1") (pin "K") (pinfunction "K_K") (pintype "passive"))
      (node (ref "L3") (pin "1") (pinfunction "1_1") (pintype "passive"))
      (node (ref "U8") (pin "3") (pinfunction "VSW_3") (pintype "input"))
    )
    (net (code "65") (name "VREG") (class "Default")
      (node (ref "C1") (pin "1") (pinfunction "1_1") (pintype "passive"))
      (node (ref "C14") (pin "1") (pinfunction "1_1") (pintype "passive"))
      (node (ref "C18") (pin "1") (pinfunction "1_1") (pintype "passive"))
      (node (ref "C6") (pin "1") (pinfunction "1_1") (pintype "passive"))
      (node (ref "C9") (pin "1") (pinfunction "1_1") (pintype "passive"))
      (node (ref "D2") (pin "A") (pinfunction "A_A") (pintype "passive"))
      (node (ref "L3") (pin "2") (pinfunction "2_2") (pintype "passive"))
      (node (ref "R5") (pin "1") (pinfunction "1_1") (pintype "passive"))
      (node (ref "U2") (pin "3") (pinfunction "IN_3") (pintype "input"))
      (node (ref "U5") (pin "3") (pinfunction "Vin_3") (pintype "passive"))
      (node (ref "U6") (pin "3") (pinfunction "Vin_3") (pintype "passive"))
    )
    (net (code "66") (name "VUNREG") (class "Default")
      (node (ref "C13") (pin "1") (pinfunction "1_1") (pintype "passive"))
      (node (ref "C15") (pin "1") (pinfunction "1_1") (pintype "passive"))
      (node (ref "U12") (pin "V+") (pinfunction "V+_V+") (pintype "passive"))
      (node (ref "U8") (pin "2") (pinfunction "VIN_2") (pintype "input"))
    )
    (net (code "67") (name "unconnected-(K1-COMMON1-Pad13)") (class "Default")
      (node (ref "K1") (pin "13") (pinfunction "COMMON1_13") (pintype "passive"))
    )
    (net (code "68") (name "unconnected-(K1-NC1-Pad11)") (class "Default")
      (node (ref "K1") (pin "11") (pinfunction "NC1_11") (pintype "passive"))
    )
    (net (code "69") (name "unconnected-(K1-NO1-Pad9)") (class "Default")
      (node (ref "K1") (pin "9") (pinfunction "NO1_9") (pintype "passive"))
    )
    (net (code "70") (name "unconnected-(K2-COMMON1-Pad13)") (class "Default")
      (node (ref "K2") (pin "13") (pinfunction "COMMON1_13") (pintype "passive"))
    )
    (net (code "71") (name "unconnected-(K2-NC1-Pad11)") (class "Default")
      (node (ref "K2") (pin "11") (pinfunction "NC1_11") (pintype "passive"))
    )
    (net (code "72") (name "unconnected-(K2-NO1-Pad9)") (class "Default")
      (node (ref "K2") (pin "9") (pinfunction "NO1_9") (pintype "passive"))
    )
    (net (code "73") (name "unconnected-(U8-SHDNB-Pad4)") (class "Default")
      (node (ref "U8") (pin "4") (pinfunction "SHDNB_4") (pintype "input"))
    )
    (net (code "74") (name "unconnected-(U8-SYNC-Pad5)") (class "Default")
      (node (ref "U8") (pin "5") (pinfunction "SYNC_5") (pintype "input"))
    )
    (net (code "75") (name "unconnected-(U22-NR-Pad4)") (class "Default")
      (node (ref "U22") (pin "4") (pinfunction "NR_4") (pintype "input"))
    )
  )
)
